# SomUSB1.net
KiCad netlist of a schematic drawn in EAGLE
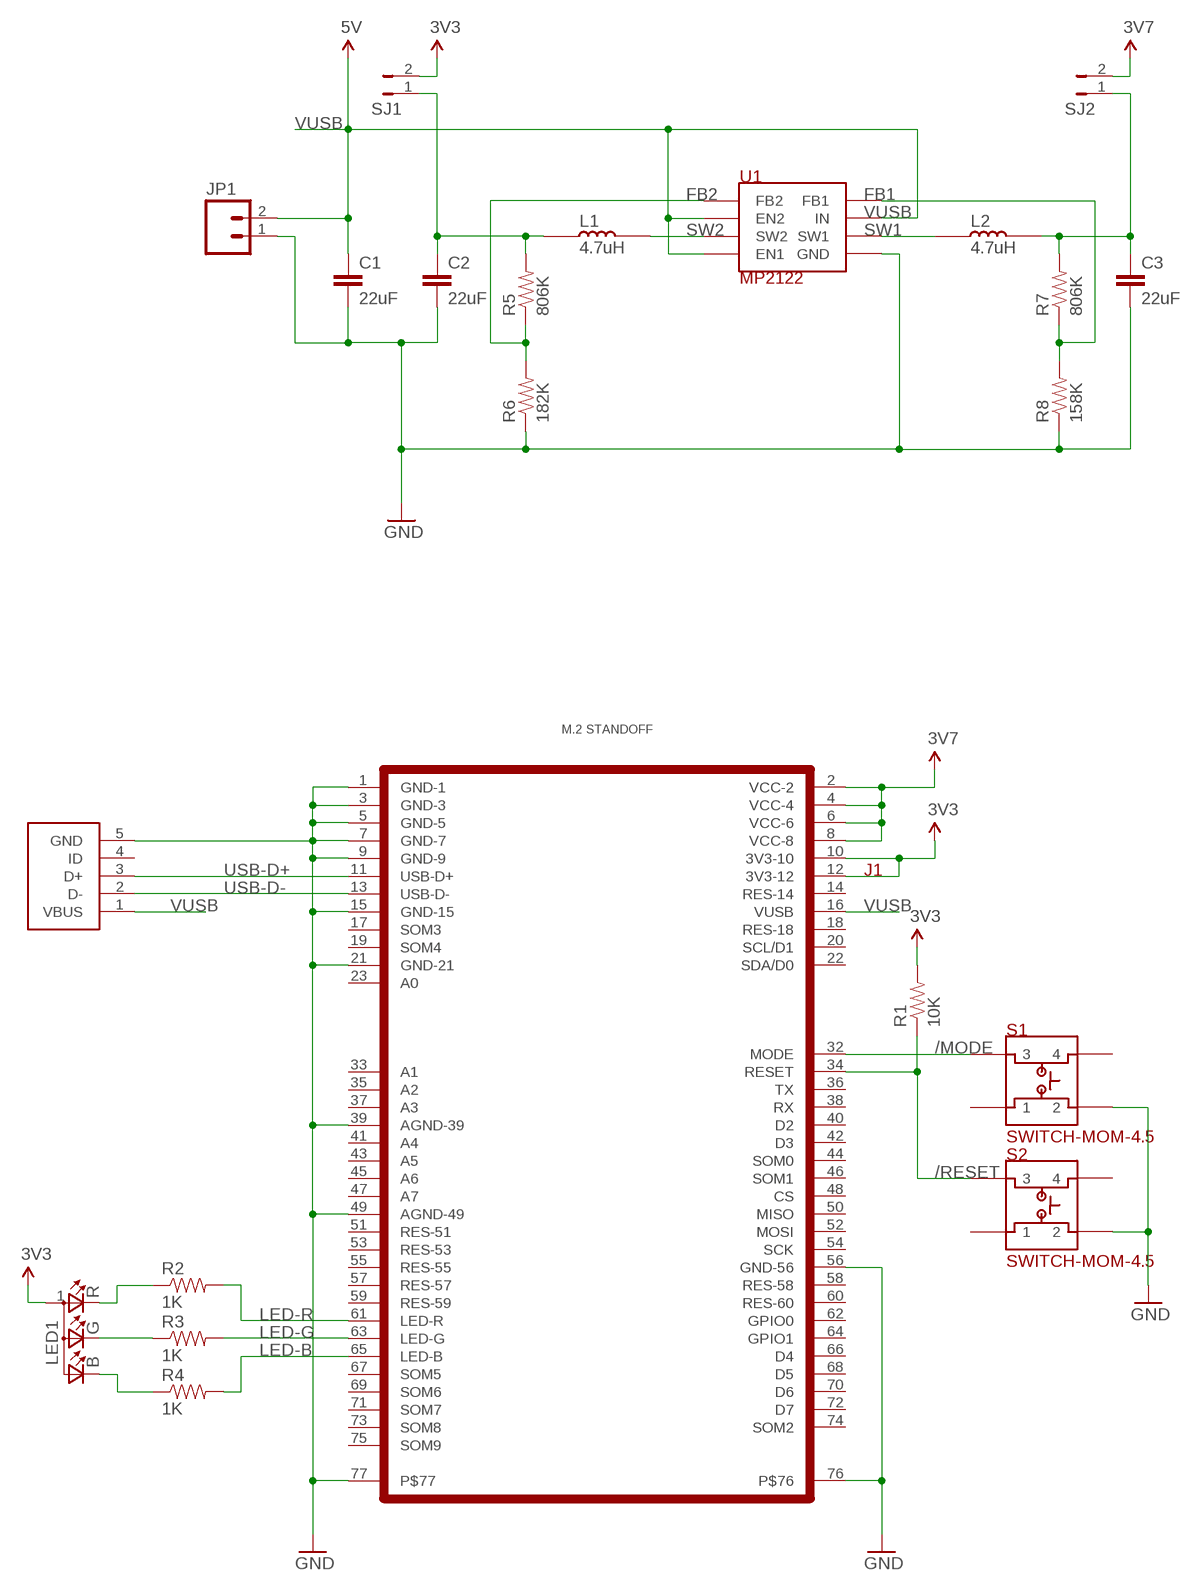
[diagram p0: schematic, sheet 1]

(export (version "E")
  (design (tool "Eeschema 10.0.6"))
  (components
    (comp (ref "C1")
      (value "22uF")
      (footprint "eagle-import:0805")
      (libsource (lib "eagle-import") (part "CAP-22UF-0805"))
    )
    (comp (ref "C2")
      (value "22uF")
      (footprint "eagle-import:0805")
      (libsource (lib "eagle-import") (part "CAP-22UF-0805"))
    )
    (comp (ref "C3")
      (value "22uF")
      (footprint "eagle-import:0805")
      (libsource (lib "eagle-import") (part "CAP-22UF-0805"))
    )
    (comp (ref "J1")
      (value "SPARK_M.2EKEY")
      (footprint "eagle-import:SPARK_M.2EKEY-LESS-CREAM")
      (libsource (lib "eagle-import") (part "SPARK_M.2EKEY"))
    )
    (comp (ref "JP1")
      (value "M02PTH")
      (footprint "eagle-import:1X02")
      (libsource (lib "eagle-import") (part "M02PTH"))
    )
    (comp (ref "L1")
      (value "4.7uH")
      (footprint "eagle-import:1008-BOURNS")
      (libsource (lib "eagle-import") (part "INDUCTOR-4.7UH"))
    )
    (comp (ref "L2")
      (value "4.7uH")
      (footprint "eagle-import:1008-BOURNS")
      (libsource (lib "eagle-import") (part "INDUCTOR-4.7UH"))
    )
    (comp (ref "LED1")
      (value "LED-RGB-CREE-SMD")
      (footprint "eagle-import:LED-RGB-CREE-SMD")
      (libsource (lib "eagle-import") (part "LED-RGB-CREE-SMD"))
    )
    (comp (ref "R1")
      (value "10K")
      (footprint "eagle-import:0603-RES")
      (libsource (lib "eagle-import") (part "RES-10K-06030603"))
    )
    (comp (ref "R2")
      (value "1K")
      (footprint "eagle-import:0603-RES")
      (libsource (lib "eagle-import") (part "RES-1K-0603"))
    )
    (comp (ref "R3")
      (value "1K")
      (footprint "eagle-import:0603-RES")
      (libsource (lib "eagle-import") (part "RES-1K-0603"))
    )
    (comp (ref "R4")
      (value "1K")
      (footprint "eagle-import:0603-RES")
      (libsource (lib "eagle-import") (part "RES-1K-0603"))
    )
    (comp (ref "R5")
      (value "806K")
      (footprint "eagle-import:0603-RES")
      (libsource (lib "eagle-import") (part "RES-806K-0603"))
    )
    (comp (ref "R6")
      (value "182K")
      (footprint "eagle-import:0603-RES")
      (libsource (lib "eagle-import") (part "RES-182K-0603"))
    )
    (comp (ref "R7")
      (value "806K")
      (footprint "eagle-import:0603-RES")
      (libsource (lib "eagle-import") (part "RES-806K-0603"))
    )
    (comp (ref "R8")
      (value "158K")
      (footprint "eagle-import:0603-RES")
      (libsource (lib "eagle-import") (part "RES-158K-0603"))
    )
    (comp (ref "S1")
      (value "SWITCH-MOM-4.5")
      (footprint "eagle-import:SWITCH-MOM-4.5")
      (libsource (lib "eagle-import") (part "SWITCH-MOM-4.5"))
    )
    (comp (ref "S2")
      (value "SWITCH-MOM-4.5")
      (footprint "eagle-import:SWITCH-MOM-4.5")
      (libsource (lib "eagle-import") (part "SWITCH-MOM-4.5"))
    )
    (comp (ref "SJ1")
      (value "JUMPER-PTH-2-NO")
      (footprint "eagle-import:PTH-JUMPER-2-NO_NO_SILK")
      (libsource (lib "eagle-import") (part "JUMPER-PTH-2-NO"))
    )
    (comp (ref "SJ2")
      (value "JUMPER-PTH-2-NO")
      (footprint "eagle-import:PTH-JUMPER-2-NO_NO_SILK")
      (libsource (lib "eagle-import") (part "JUMPER-PTH-2-NO"))
    )
    (comp (ref "U$1")
      (value "M2-STANDOFF")
      (footprint "eagle-import:M2-STANDOFF")
      (libsource (lib "eagle-import") (part "M2-STANDOFF"))
    )
    (comp (ref "U$3")
      (value "USB-MICRO-B-SOCKET-AMPHENOL")
      (footprint "eagle-import:USB-B-SMT-AMPHENOL")
      (libsource (lib "eagle-import") (part "USB-MICRO-B-SOCKET-AMPHENOL"))
    )
    (comp (ref "U1")
      (value "MP2122")
      (footprint "eagle-import:TSOT23-8-MPS")
      (libsource (lib "eagle-import") (part "MPS2112"))
    )
  )
  (nets
    (net (code "1") (name "/FB1") (class "Default")
      (node (ref "R7") (pin "1") (pinfunction "1_1") (pintype "passive"))
      (node (ref "R8") (pin "2") (pinfunction "2_2") (pintype "passive"))
      (node (ref "U1") (pin "8") (pinfunction "FB1_8") (pintype "input"))
    )
    (net (code "2") (name "/FB2") (class "Default")
      (node (ref "R5") (pin "1") (pinfunction "1_1") (pintype "passive"))
      (node (ref "R6") (pin "2") (pinfunction "2_2") (pintype "passive"))
      (node (ref "U1") (pin "1") (pinfunction "FB2_1") (pintype "input"))
    )
    (net (code "3") (name "/LED-B") (class "Default")
      (node (ref "J1") (pin "65") (pinfunction "LED-B_65") (pintype "bidirectional"))
      (node (ref "R4") (pin "2") (pinfunction "2_2") (pintype "passive"))
    )
    (net (code "4") (name "/LED-G") (class "Default")
      (node (ref "J1") (pin "63") (pinfunction "LED-G_63") (pintype "bidirectional"))
      (node (ref "R3") (pin "2") (pinfunction "2_2") (pintype "passive"))
    )
    (net (code "5") (name "/LED-R") (class "Default")
      (node (ref "J1") (pin "61") (pinfunction "LED-R_61") (pintype "bidirectional"))
      (node (ref "R2") (pin "2") (pinfunction "2_2") (pintype "passive"))
    )
    (net (code "6") (name "/SW1") (class "Default")
      (node (ref "L2") (pin "1") (pinfunction "P$1_1") (pintype "passive"))
      (node (ref "U1") (pin "6") (pinfunction "SW1_6") (pintype "output"))
    )
    (net (code "7") (name "/SW2") (class "Default")
      (node (ref "L1") (pin "2") (pinfunction "P$2_2") (pintype "passive"))
      (node (ref "U1") (pin "3") (pinfunction "SW2_3") (pintype "output"))
    )
    (net (code "8") (name "/USB-D+") (class "Default")
      (node (ref "J1") (pin "11") (pinfunction "USB-D+_11") (pintype "bidirectional"))
      (node (ref "U$3") (pin "3") (pinfunction "D+_3") (pintype "passive"))
    )
    (net (code "9") (name "/USB-D-") (class "Default")
      (node (ref "J1") (pin "13") (pinfunction "USB-D-_13") (pintype "bidirectional"))
      (node (ref "U$3") (pin "2") (pinfunction "D-_2") (pintype "passive"))
    )
    (net (code "10") (name "/{slash}MODE") (class "Default")
      (node (ref "J1") (pin "32") (pinfunction "MODE_32") (pintype "bidirectional"))
      (node (ref "S1") (pin "3") (pinfunction "3_3") (pintype "passive"))
    )
    (net (code "11") (name "/{slash}RESET") (class "Default")
      (node (ref "J1") (pin "34") (pinfunction "RESET_34") (pintype "bidirectional"))
      (node (ref "R1") (pin "1") (pinfunction "1_1") (pintype "passive"))
      (node (ref "S2") (pin "3") (pinfunction "3_3") (pintype "passive"))
    )
    (net (code "12") (name "3V3") (class "Default")
      (node (ref "J1") (pin "10") (pinfunction "3V3-10_10") (pintype "bidirectional"))
      (node (ref "J1") (pin "12") (pinfunction "3V3-12_12") (pintype "bidirectional"))
      (node (ref "LED1") (pin "1") (pinfunction "A_1") (pintype "passive"))
      (node (ref "R1") (pin "2") (pinfunction "2_2") (pintype "passive"))
      (node (ref "SJ1") (pin "2") (pinfunction "2_2") (pintype "passive"))
    )
    (net (code "13") (name "3V7") (class "Default")
      (node (ref "J1") (pin "2") (pinfunction "VCC-2_2") (pintype "bidirectional"))
      (node (ref "J1") (pin "4") (pinfunction "VCC-4_4") (pintype "bidirectional"))
      (node (ref "J1") (pin "6") (pinfunction "VCC-6_6") (pintype "bidirectional"))
      (node (ref "J1") (pin "8") (pinfunction "VCC-8_8") (pintype "bidirectional"))
      (node (ref "SJ2") (pin "2") (pinfunction "2_2") (pintype "passive"))
    )
    (net (code "14") (name "5V") (class "Default")
      (node (ref "C1") (pin "1") (pinfunction "1_1") (pintype "passive"))
      (node (ref "J1") (pin "16") (pinfunction "VUSB_16") (pintype "bidirectional"))
      (node (ref "JP1") (pin "2") (pinfunction "2_2") (pintype "passive"))
      (node (ref "U$3") (pin "1") (pinfunction "VBUS_1") (pintype "passive"))
      (node (ref "U1") (pin "2") (pinfunction "EN2_2") (pintype "input"))
      (node (ref "U1") (pin "4") (pinfunction "EN1_4") (pintype "input"))
      (node (ref "U1") (pin "7") (pinfunction "IN_7") (pintype "input"))
    )
    (net (code "15") (name "GND") (class "Default")
      (node (ref "C1") (pin "2") (pinfunction "2_2") (pintype "passive"))
      (node (ref "C2") (pin "2") (pinfunction "2_2") (pintype "passive"))
      (node (ref "C3") (pin "2") (pinfunction "2_2") (pintype "passive"))
      (node (ref "J1") (pin "1") (pinfunction "GND-1_1") (pintype "bidirectional"))
      (node (ref "J1") (pin "15") (pinfunction "GND-15_15") (pintype "bidirectional"))
      (node (ref "J1") (pin "21") (pinfunction "GND-21_21") (pintype "bidirectional"))
      (node (ref "J1") (pin "3") (pinfunction "GND-3_3") (pintype "bidirectional"))
      (node (ref "J1") (pin "39") (pinfunction "AGND-39_39") (pintype "bidirectional"))
      (node (ref "J1") (pin "49") (pinfunction "AGND-49_49") (pintype "bidirectional"))
      (node (ref "J1") (pin "5") (pinfunction "GND-5_5") (pintype "bidirectional"))
      (node (ref "J1") (pin "56") (pinfunction "GND-56_56") (pintype "bidirectional"))
      (node (ref "J1") (pin "7") (pinfunction "GND-7_7") (pintype "bidirectional"))
      (node (ref "J1") (pin "76") (pinfunction "P$76_76") (pintype "power_in"))
      (node (ref "J1") (pin "77") (pinfunction "P$77_77") (pintype "power_in"))
      (node (ref "J1") (pin "9") (pinfunction "GND-9_9") (pintype "bidirectional"))
      (node (ref "JP1") (pin "1") (pinfunction "1_1") (pintype "passive"))
      (node (ref "R6") (pin "1") (pinfunction "1_1") (pintype "passive"))
      (node (ref "R8") (pin "1") (pinfunction "1_1") (pintype "passive"))
      (node (ref "S1") (pin "2") (pinfunction "2_2") (pintype "passive"))
      (node (ref "S2") (pin "2") (pinfunction "2_2") (pintype "passive"))
      (node (ref "U$3") (pin "5") (pinfunction "GND_5") (pintype "passive"))
      (node (ref "U1") (pin "5") (pinfunction "GND_5") (pintype "passive"))
    )
    (net (code "16") (name "Net-(L1-P$1)") (class "Default")
      (node (ref "C2") (pin "1") (pinfunction "1_1") (pintype "passive"))
      (node (ref "L1") (pin "1") (pinfunction "P$1_1") (pintype "passive"))
      (node (ref "R5") (pin "2") (pinfunction "2_2") (pintype "passive"))
      (node (ref "SJ1") (pin "1") (pinfunction "1_1") (pintype "passive"))
    )
    (net (code "17") (name "Net-(L2-P$2)") (class "Default")
      (node (ref "C3") (pin "1") (pinfunction "1_1") (pintype "passive"))
      (node (ref "L2") (pin "2") (pinfunction "P$2_2") (pintype "passive"))
      (node (ref "R7") (pin "2") (pinfunction "2_2") (pintype "passive"))
      (node (ref "SJ2") (pin "1") (pinfunction "1_1") (pintype "passive"))
    )
    (net (code "18") (name "Net-(LED1-B)") (class "Default")
      (node (ref "LED1") (pin "2") (pinfunction "B_2") (pintype "passive"))
      (node (ref "R4") (pin "1") (pinfunction "1_1") (pintype "passive"))
    )
    (net (code "19") (name "Net-(LED1-G)") (class "Default")
      (node (ref "LED1") (pin "3") (pinfunction "G_3") (pintype "passive"))
      (node (ref "R3") (pin "1") (pinfunction "1_1") (pintype "passive"))
    )
    (net (code "20") (name "Net-(LED1-R)") (class "Default")
      (node (ref "LED1") (pin "4") (pinfunction "R_4") (pintype "passive"))
      (node (ref "R2") (pin "1") (pinfunction "1_1") (pintype "passive"))
    )
    (net (code "21") (name "unconnected-(J1-A0-Pad23)") (class "Default")
      (node (ref "J1") (pin "23") (pinfunction "A0_23") (pintype "bidirectional"))
    )
    (net (code "22") (name "unconnected-(J1-A1-Pad33)") (class "Default")
      (node (ref "J1") (pin "33") (pinfunction "A1_33") (pintype "bidirectional"))
    )
    (net (code "23") (name "unconnected-(J1-A2-Pad35)") (class "Default")
      (node (ref "J1") (pin "35") (pinfunction "A2_35") (pintype "bidirectional"))
    )
    (net (code "24") (name "unconnected-(J1-A3-Pad37)") (class "Default")
      (node (ref "J1") (pin "37") (pinfunction "A3_37") (pintype "bidirectional"))
    )
    (net (code "25") (name "unconnected-(J1-A4-Pad41)") (class "Default")
      (node (ref "J1") (pin "41") (pinfunction "A4_41") (pintype "bidirectional"))
    )
    (net (code "26") (name "unconnected-(J1-A5-Pad43)") (class "Default")
      (node (ref "J1") (pin "43") (pinfunction "A5_43") (pintype "bidirectional"))
    )
    (net (code "27") (name "unconnected-(J1-A6-Pad45)") (class "Default")
      (node (ref "J1") (pin "45") (pinfunction "A6_45") (pintype "bidirectional"))
    )
    (net (code "28") (name "unconnected-(J1-A7-Pad47)") (class "Default")
      (node (ref "J1") (pin "47") (pinfunction "A7_47") (pintype "bidirectional"))
    )
    (net (code "29") (name "unconnected-(J1-CS-Pad48)") (class "Default")
      (node (ref "J1") (pin "48") (pinfunction "CS_48") (pintype "bidirectional"))
    )
    (net (code "30") (name "unconnected-(J1-D2-Pad40)") (class "Default")
      (node (ref "J1") (pin "40") (pinfunction "D2_40") (pintype "bidirectional"))
    )
    (net (code "31") (name "unconnected-(J1-D3-Pad42)") (class "Default")
      (node (ref "J1") (pin "42") (pinfunction "D3_42") (pintype "bidirectional"))
    )
    (net (code "32") (name "unconnected-(J1-D4-Pad66)") (class "Default")
      (node (ref "J1") (pin "66") (pinfunction "D4_66") (pintype "bidirectional"))
    )
    (net (code "33") (name "unconnected-(J1-D5-Pad68)") (class "Default")
      (node (ref "J1") (pin "68") (pinfunction "D5_68") (pintype "bidirectional"))
    )
    (net (code "34") (name "unconnected-(J1-D6-Pad70)") (class "Default")
      (node (ref "J1") (pin "70") (pinfunction "D6_70") (pintype "bidirectional"))
    )
    (net (code "35") (name "unconnected-(J1-D7-Pad72)") (class "Default")
      (node (ref "J1") (pin "72") (pinfunction "D7_72") (pintype "bidirectional"))
    )
    (net (code "36") (name "unconnected-(J1-GPIO0-Pad62)") (class "Default")
      (node (ref "J1") (pin "62") (pinfunction "GPIO0_62") (pintype "bidirectional"))
    )
    (net (code "37") (name "unconnected-(J1-GPIO1-Pad64)") (class "Default")
      (node (ref "J1") (pin "64") (pinfunction "GPIO1_64") (pintype "bidirectional"))
    )
    (net (code "38") (name "unconnected-(J1-MISO-Pad50)") (class "Default")
      (node (ref "J1") (pin "50") (pinfunction "MISO_50") (pintype "bidirectional"))
    )
    (net (code "39") (name "unconnected-(J1-MOSI-Pad52)") (class "Default")
      (node (ref "J1") (pin "52") (pinfunction "MOSI_52") (pintype "bidirectional"))
    )
    (net (code "40") (name "unconnected-(J1-RES-14-Pad14)") (class "Default")
      (node (ref "J1") (pin "14") (pinfunction "RES-14_14") (pintype "bidirectional"))
    )
    (net (code "41") (name "unconnected-(J1-RES-18-Pad18)") (class "Default")
      (node (ref "J1") (pin "18") (pinfunction "RES-18_18") (pintype "bidirectional"))
    )
    (net (code "42") (name "unconnected-(J1-RES-51-Pad51)") (class "Default")
      (node (ref "J1") (pin "51") (pinfunction "RES-51_51") (pintype "bidirectional"))
    )
    (net (code "43") (name "unconnected-(J1-RES-53-Pad53)") (class "Default")
      (node (ref "J1") (pin "53") (pinfunction "RES-53_53") (pintype "bidirectional"))
    )
    (net (code "44") (name "unconnected-(J1-RES-55-Pad55)") (class "Default")
      (node (ref "J1") (pin "55") (pinfunction "RES-55_55") (pintype "bidirectional"))
    )
    (net (code "45") (name "unconnected-(J1-RES-57-Pad57)") (class "Default")
      (node (ref "J1") (pin "57") (pinfunction "RES-57_57") (pintype "bidirectional"))
    )
    (net (code "46") (name "unconnected-(J1-RES-58-Pad58)") (class "Default")
      (node (ref "J1") (pin "58") (pinfunction "RES-58_58") (pintype "bidirectional"))
    )
    (net (code "47") (name "unconnected-(J1-RES-59-Pad59)") (class "Default")
      (node (ref "J1") (pin "59") (pinfunction "RES-59_59") (pintype "bidirectional"))
    )
    (net (code "48") (name "unconnected-(J1-RES-60-Pad60)") (class "Default")
      (node (ref "J1") (pin "60") (pinfunction "RES-60_60") (pintype "bidirectional"))
    )
    (net (code "49") (name "unconnected-(J1-RX-Pad38)") (class "Default")
      (node (ref "J1") (pin "38") (pinfunction "RX_38") (pintype "bidirectional"))
    )
    (net (code "50") (name "unconnected-(J1-SCK-Pad54)") (class "Default")
      (node (ref "J1") (pin "54") (pinfunction "SCK_54") (pintype "bidirectional"))
    )
    (net (code "51") (name "unconnected-(J1-SCL{slash}D1-Pad20)") (class "Default")
      (node (ref "J1") (pin "20") (pinfunction "SCL/D1_20") (pintype "bidirectional"))
    )
    (net (code "52") (name "unconnected-(J1-SDA{slash}D0-Pad22)") (class "Default")
      (node (ref "J1") (pin "22") (pinfunction "SDA/D0_22") (pintype "bidirectional"))
    )
    (net (code "53") (name "unconnected-(J1-SOM0-Pad44)") (class "Default")
      (node (ref "J1") (pin "44") (pinfunction "SOM0_44") (pintype "bidirectional"))
    )
    (net (code "54") (name "unconnected-(J1-SOM1-Pad46)") (class "Default")
      (node (ref "J1") (pin "46") (pinfunction "SOM1_46") (pintype "bidirectional"))
    )
    (net (code "55") (name "unconnected-(J1-SOM2-Pad74)") (class "Default")
      (node (ref "J1") (pin "74") (pinfunction "SOM2_74") (pintype "bidirectional"))
    )
    (net (code "56") (name "unconnected-(J1-SOM3-Pad17)") (class "Default")
      (node (ref "J1") (pin "17") (pinfunction "SOM3_17") (pintype "bidirectional"))
    )
    (net (code "57") (name "unconnected-(J1-SOM4-Pad19)") (class "Default")
      (node (ref "J1") (pin "19") (pinfunction "SOM4_19") (pintype "bidirectional"))
    )
    (net (code "58") (name "unconnected-(J1-SOM5-Pad67)") (class "Default")
      (node (ref "J1") (pin "67") (pinfunction "SOM5_67") (pintype "bidirectional"))
    )
    (net (code "59") (name "unconnected-(J1-SOM6-Pad69)") (class "Default")
      (node (ref "J1") (pin "69") (pinfunction "SOM6_69") (pintype "bidirectional"))
    )
    (net (code "60") (name "unconnected-(J1-SOM7-Pad71)") (class "Default")
      (node (ref "J1") (pin "71") (pinfunction "SOM7_71") (pintype "bidirectional"))
    )
    (net (code "61") (name "unconnected-(J1-SOM8-Pad73)") (class "Default")
      (node (ref "J1") (pin "73") (pinfunction "SOM8_73") (pintype "bidirectional"))
    )
    (net (code "62") (name "unconnected-(J1-SOM9-Pad75)") (class "Default")
      (node (ref "J1") (pin "75") (pinfunction "SOM9_75") (pintype "bidirectional"))
    )
    (net (code "63") (name "unconnected-(J1-TX-Pad36)") (class "Default")
      (node (ref "J1") (pin "36") (pinfunction "TX_36") (pintype "bidirectional"))
    )
    (net (code "64") (name "unconnected-(S1-Pad1)") (class "Default")
      (node (ref "S1") (pin "1") (pinfunction "1_1") (pintype "passive"))
    )
    (net (code "65") (name "unconnected-(S1-Pad4)") (class "Default")
      (node (ref "S1") (pin "4") (pinfunction "4_4") (pintype "passive"))
    )
    (net (code "66") (name "unconnected-(S2-Pad1)") (class "Default")
      (node (ref "S2") (pin "1") (pinfunction "1_1") (pintype "passive"))
    )
    (net (code "67") (name "unconnected-(S2-Pad4)") (class "Default")
      (node (ref "S2") (pin "4") (pinfunction "4_4") (pintype "passive"))
    )
    (net (code "68") (name "unconnected-(U$3-ID-Pad4)") (class "Default")
      (node (ref "U$3") (pin "4") (pinfunction "ID_4") (pintype "passive"))
    )
  )
)
